# IntegratedSensor.net
KiCad netlist of a schematic drawn in EAGLE
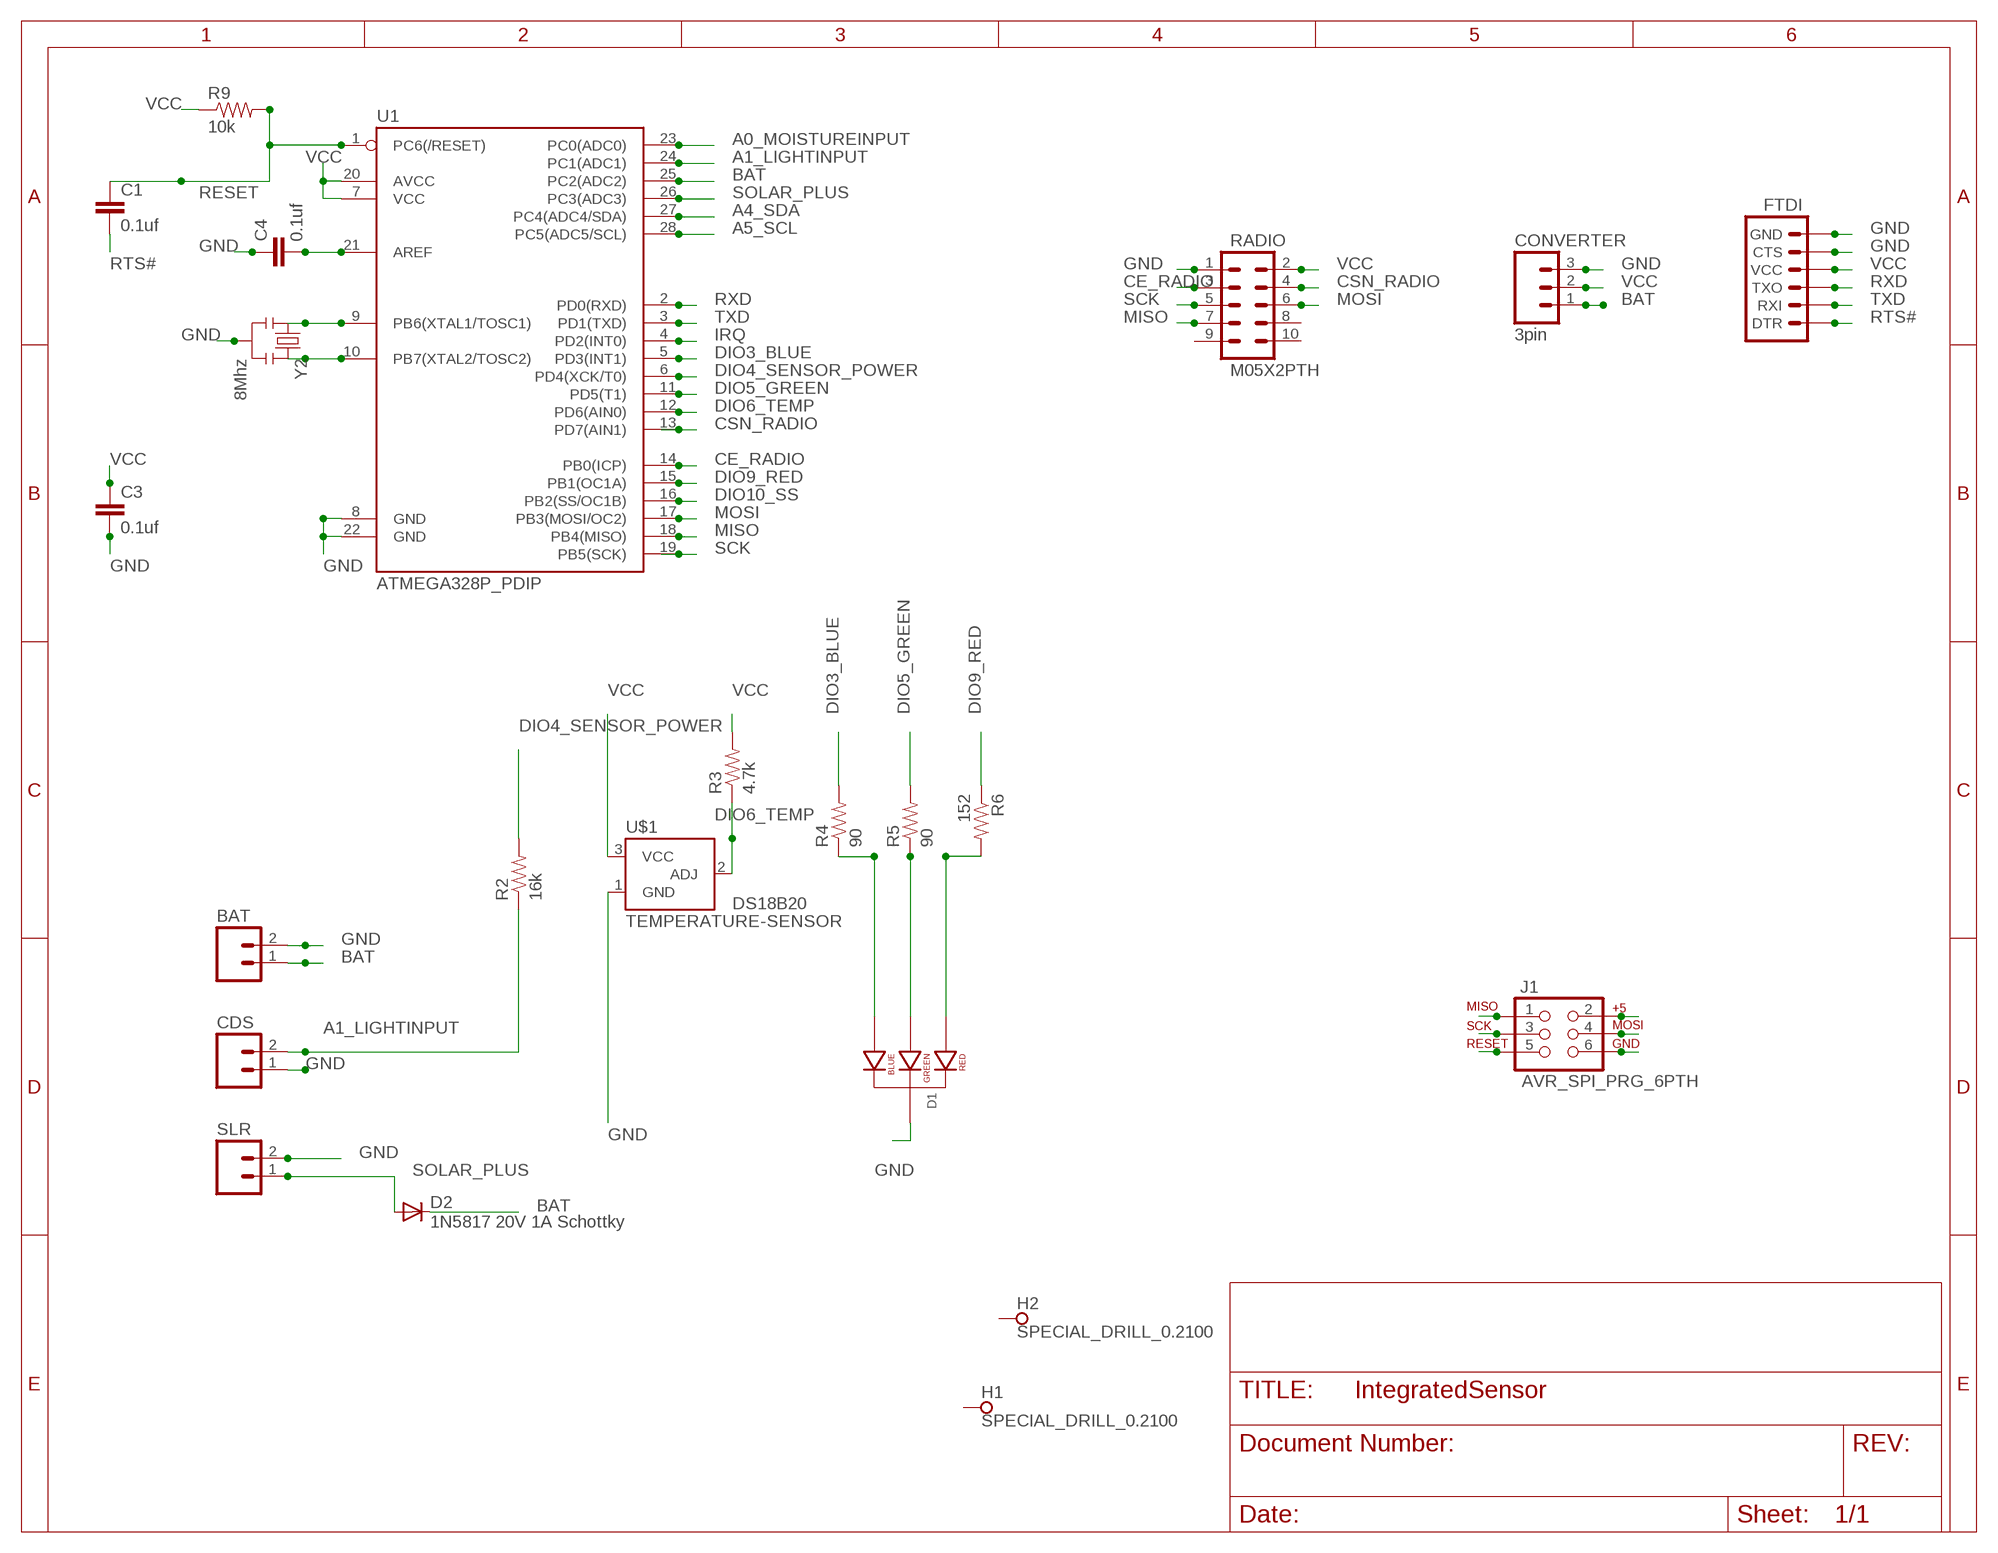
[diagram p0: schematic, sheet 1]

(export (version "E")
  (design (tool "Eeschema 10.0.6"))
  (components
    (comp (ref "BAT")
      (value "M02PTH")
      (footprint "eagle-import:1X02")
      (libsource (lib "eagle-import") (part "M02PTH"))
    )
    (comp (ref "C1")
      (value "0.1uf")
      (footprint "eagle-import:CAP-PTH-SMALL")
      (libsource (lib "eagle-import") (part "CAPPTH"))
    )
    (comp (ref "C3")
      (value "0.1uf")
      (footprint "eagle-import:CAP-PTH-SMALL")
      (libsource (lib "eagle-import") (part "CAPPTH"))
    )
    (comp (ref "C4")
      (value "0.1uf")
      (footprint "eagle-import:CAP-PTH-SMALL")
      (libsource (lib "eagle-import") (part "CAPPTH"))
    )
    (comp (ref "CDS")
      (value "M02PTH")
      (footprint "eagle-import:1X02")
      (libsource (lib "eagle-import") (part "M02PTH"))
    )
    (comp (ref "CONVERTER")
      (value "3pin")
      (footprint "eagle-import:1X03")
      (libsource (lib "eagle-import") (part "M03PTH"))
    )
    (comp (ref "D1")
      (value "LED-RGB-CC-THRUCLEAR")
      (footprint "eagle-import:LED-RGB-THRU")
      (libsource (lib "eagle-import") (part "LED-RGB-CC-THRUCLEAR"))
    )
    (comp (ref "D2")
      (value "1N5817 20V 1A Schottky")
      (footprint "eagle-import:DIODE-1N4001")
      (libsource (lib "eagle-import") (part "DIODEPTH"))
    )
    (comp (ref "FTDI")
      (value "ARDUINO_SERIAL_PROGRAMPTH")
      (footprint "eagle-import:1X06")
      (libsource (lib "eagle-import") (part "ARDUINO_SERIAL_PROGRAMPTH"))
    )
    (comp (ref "H1")
      (value "SPECIAL_DRILL_0.2100")
      (footprint "eagle-import:PAD_0.2100")
      (libsource (lib "eagle-import") (part "SPECIAL_DRILL_0.2100"))
    )
    (comp (ref "H2")
      (value "SPECIAL_DRILL_0.2100")
      (footprint "eagle-import:PAD_0.2100")
      (libsource (lib "eagle-import") (part "SPECIAL_DRILL_0.2100"))
    )
    (comp (ref "J1")
      (value "AVR_SPI_PRG_6PTH")
      (footprint "eagle-import:2X3")
      (libsource (lib "eagle-import") (part "AVR_SPI_PRG_6PTH"))
    )
    (comp (ref "R2")
      (value "16k")
      (footprint "eagle-import:1_6W-RES")
      (libsource (lib "eagle-import") (part "RESISTORPTH-1/6W"))
    )
    (comp (ref "R3")
      (value "4.7k")
      (footprint "eagle-import:1_6W-RES")
      (libsource (lib "eagle-import") (part "RESISTORPTH-1/6W"))
    )
    (comp (ref "R4")
      (value "90")
      (footprint "eagle-import:1_6W-RES")
      (libsource (lib "eagle-import") (part "RESISTORPTH-1/6W"))
    )
    (comp (ref "R5")
      (value "90")
      (footprint "eagle-import:1_6W-RES")
      (libsource (lib "eagle-import") (part "RESISTORPTH-1/6W"))
    )
    (comp (ref "R6")
      (value "152")
      (footprint "eagle-import:1_6W-RES")
      (libsource (lib "eagle-import") (part "RESISTORPTH-1/6W"))
    )
    (comp (ref "R9")
      (value "10k")
      (footprint "eagle-import:1_6W-RES")
      (libsource (lib "eagle-import") (part "RESISTORPTH-1/6W"))
    )
    (comp (ref "RADIO")
      (value "M05X2PTH")
      (footprint "eagle-import:AVR_ICSP")
      (libsource (lib "eagle-import") (part "M05X2PTH"))
    )
    (comp (ref "SLR")
      (value "M02PTH")
      (footprint "eagle-import:1X02")
      (libsource (lib "eagle-import") (part "M02PTH"))
    )
    (comp (ref "U$1")
      (value "TEMPERATURE-SENSOR")
      (footprint "eagle-import:TO-92")
      (fields (field (name "PARTNAME") "DS18B20"))
      (libsource (lib "eagle-import") (part "TEMPERATURE-SENSOR"))
    )
    (comp (ref "U1")
      (value "ATMEGA328P_PDIP")
      (footprint "eagle-import:DIL28-3")
      (libsource (lib "eagle-import") (part "ATMEGA328P_PDIP"))
    )
    (comp (ref "Y2")
      (value "8Mhz")
      (footprint "eagle-import:RESONATOR-PTH")
      (libsource (lib "eagle-import") (part "RESONATORPTH"))
    )
  )
  (nets
    (net (code "1") (name "/A0_MOISTUREINPUT") (class "Default")
      (node (ref "U1") (pin "23") (pinfunction "PC0(ADC0)_23") (pintype "bidirectional"))
    )
    (net (code "2") (name "/A1_LIGHTINPUT") (class "Default")
      (node (ref "CDS") (pin "2") (pinfunction "2_2") (pintype "passive"))
      (node (ref "R2") (pin "1") (pinfunction "1_1") (pintype "passive"))
      (node (ref "U1") (pin "24") (pinfunction "PC1(ADC1)_24") (pintype "bidirectional"))
    )
    (net (code "3") (name "/A4_SDA") (class "Default")
      (node (ref "U1") (pin "27") (pinfunction "PC4(ADC4/SDA)_27") (pintype "bidirectional"))
    )
    (net (code "4") (name "/A5_SCL") (class "Default")
      (node (ref "U1") (pin "28") (pinfunction "PC5(ADC5/SCL)_28") (pintype "bidirectional"))
    )
    (net (code "5") (name "/BAT") (class "Default")
      (node (ref "BAT") (pin "1") (pinfunction "1_1") (pintype "passive"))
      (node (ref "CONVERTER") (pin "1") (pinfunction "1_1") (pintype "passive"))
      (node (ref "D2") (pin "C") (pinfunction "C_C") (pintype "passive"))
      (node (ref "U1") (pin "25") (pinfunction "PC2(ADC2)_25") (pintype "bidirectional"))
    )
    (net (code "6") (name "/CE_RADIO") (class "Default")
      (node (ref "RADIO") (pin "3") (pinfunction "3_3") (pintype "passive"))
      (node (ref "U1") (pin "14") (pinfunction "PB0(ICP)_14") (pintype "bidirectional"))
    )
    (net (code "7") (name "/CSN_RADIO") (class "Default")
      (node (ref "RADIO") (pin "4") (pinfunction "4_4") (pintype "passive"))
      (node (ref "U1") (pin "13") (pinfunction "PD7(AIN1)_13") (pintype "bidirectional"))
    )
    (net (code "8") (name "/DIO3_BLUE") (class "Default")
      (node (ref "R4") (pin "2") (pinfunction "2_2") (pintype "passive"))
      (node (ref "U1") (pin "5") (pinfunction "PD3(INT1)_5") (pintype "bidirectional"))
    )
    (net (code "9") (name "/DIO4_SENSOR_POWER") (class "Default")
      (node (ref "R2") (pin "2") (pinfunction "2_2") (pintype "passive"))
      (node (ref "U1") (pin "6") (pinfunction "PD4(XCK/T0)_6") (pintype "bidirectional"))
    )
    (net (code "10") (name "/DIO5_GREEN") (class "Default")
      (node (ref "R5") (pin "2") (pinfunction "2_2") (pintype "passive"))
      (node (ref "U1") (pin "11") (pinfunction "PD5(T1)_11") (pintype "bidirectional"))
    )
    (net (code "11") (name "/DIO6_TEMP") (class "Default")
      (node (ref "R3") (pin "1") (pinfunction "1_1") (pintype "passive"))
      (node (ref "U$1") (pin "2") (pinfunction "ADJ_2") (pintype "bidirectional"))
      (node (ref "U1") (pin "12") (pinfunction "PD6(AIN0)_12") (pintype "bidirectional"))
    )
    (net (code "12") (name "/DIO9_RED") (class "Default")
      (node (ref "R6") (pin "1") (pinfunction "1_1") (pintype "passive"))
      (node (ref "U1") (pin "15") (pinfunction "PB1(OC1A)_15") (pintype "bidirectional"))
    )
    (net (code "13") (name "/DIO10_SS") (class "Default")
      (node (ref "U1") (pin "16") (pinfunction "PB2(SS/OC1B)_16") (pintype "bidirectional"))
    )
    (net (code "14") (name "/GND") (class "Default")
      (node (ref "BAT") (pin "2") (pinfunction "2_2") (pintype "passive"))
      (node (ref "C3") (pin "2") (pinfunction "2_2") (pintype "passive"))
      (node (ref "C4") (pin "1") (pinfunction "1_1") (pintype "passive"))
      (node (ref "CDS") (pin "1") (pinfunction "1_1") (pintype "passive"))
      (node (ref "CONVERTER") (pin "3") (pinfunction "3_3") (pintype "passive"))
      (node (ref "D1") (pin "2") (pinfunction "CATHODE_2") (pintype "bidirectional"))
      (node (ref "FTDI") (pin "5") (pinfunction "CTS_5") (pintype "passive"))
      (node (ref "FTDI") (pin "6") (pinfunction "GND_6") (pintype "passive"))
      (node (ref "J1") (pin "6") (pinfunction "6_6") (pintype "passive"))
      (node (ref "RADIO") (pin "1") (pinfunction "1_1") (pintype "passive"))
      (node (ref "SLR") (pin "2") (pinfunction "2_2") (pintype "passive"))
      (node (ref "U$1") (pin "1") (pinfunction "GND_1") (pintype "bidirectional"))
      (node (ref "U1") (pin "22") (pinfunction "GND_22") (pintype "bidirectional"))
      (node (ref "U1") (pin "8") (pinfunction "GND_8") (pintype "bidirectional"))
      (node (ref "Y2") (pin "2") (pinfunction "2_2") (pintype "passive"))
    )
    (net (code "15") (name "/IRQ") (class "Default")
      (node (ref "U1") (pin "4") (pinfunction "PD2(INT0)_4") (pintype "bidirectional"))
    )
    (net (code "16") (name "/MISO") (class "Default")
      (node (ref "J1") (pin "1") (pinfunction "1_1") (pintype "passive"))
      (node (ref "RADIO") (pin "7") (pinfunction "7_7") (pintype "passive"))
      (node (ref "U1") (pin "18") (pinfunction "PB4(MISO)_18") (pintype "bidirectional"))
    )
    (net (code "17") (name "/MOSI") (class "Default")
      (node (ref "J1") (pin "4") (pinfunction "4_4") (pintype "passive"))
      (node (ref "RADIO") (pin "6") (pinfunction "6_6") (pintype "passive"))
      (node (ref "U1") (pin "17") (pinfunction "PB3(MOSI/OC2)_17") (pintype "bidirectional"))
    )
    (net (code "18") (name "/RESET") (class "Default")
      (node (ref "C1") (pin "1") (pinfunction "1_1") (pintype "passive"))
      (node (ref "J1") (pin "5") (pinfunction "5_5") (pintype "passive"))
      (node (ref "R9") (pin "2") (pinfunction "2_2") (pintype "passive"))
      (node (ref "U1") (pin "1") (pinfunction "PC6(/RESET)_1") (pintype "bidirectional"))
    )
    (net (code "19") (name "/RTS#") (class "Default")
      (node (ref "C1") (pin "2") (pinfunction "2_2") (pintype "passive"))
      (node (ref "FTDI") (pin "1") (pinfunction "DTR_1") (pintype "passive"))
    )
    (net (code "20") (name "/RXD") (class "Default")
      (node (ref "FTDI") (pin "3") (pinfunction "TXO_3") (pintype "passive"))
      (node (ref "U1") (pin "2") (pinfunction "PD0(RXD)_2") (pintype "bidirectional"))
    )
    (net (code "21") (name "/SCK") (class "Default")
      (node (ref "J1") (pin "3") (pinfunction "3_3") (pintype "passive"))
      (node (ref "RADIO") (pin "5") (pinfunction "5_5") (pintype "passive"))
      (node (ref "U1") (pin "19") (pinfunction "PB5(SCK)_19") (pintype "bidirectional"))
    )
    (net (code "22") (name "/SOLAR_PLUS") (class "Default")
      (node (ref "D2") (pin "A") (pinfunction "A_A") (pintype "passive"))
      (node (ref "SLR") (pin "1") (pinfunction "1_1") (pintype "passive"))
      (node (ref "U1") (pin "26") (pinfunction "PC3(ADC3)_26") (pintype "bidirectional"))
    )
    (net (code "23") (name "/TXD") (class "Default")
      (node (ref "FTDI") (pin "2") (pinfunction "RXI_2") (pintype "passive"))
      (node (ref "U1") (pin "3") (pinfunction "PD1(TXD)_3") (pintype "bidirectional"))
    )
    (net (code "24") (name "/VCC") (class "Default")
      (node (ref "C3") (pin "1") (pinfunction "1_1") (pintype "passive"))
      (node (ref "CONVERTER") (pin "2") (pinfunction "2_2") (pintype "passive"))
      (node (ref "FTDI") (pin "4") (pinfunction "VCC_4") (pintype "passive"))
      (node (ref "J1") (pin "2") (pinfunction "2_2") (pintype "passive"))
      (node (ref "R3") (pin "2") (pinfunction "2_2") (pintype "passive"))
      (node (ref "R9") (pin "1") (pinfunction "1_1") (pintype "passive"))
      (node (ref "RADIO") (pin "2") (pinfunction "2_2") (pintype "passive"))
      (node (ref "U$1") (pin "3") (pinfunction "VCC_3") (pintype "bidirectional"))
      (node (ref "U1") (pin "20") (pinfunction "AVCC_20") (pintype "bidirectional"))
      (node (ref "U1") (pin "7") (pinfunction "VCC_7") (pintype "bidirectional"))
    )
    (net (code "25") (name "Net-(D1-BLUE_CATHODE)") (class "Default")
      (node (ref "D1") (pin "4") (pinfunction "BLUE_CATHODE_4") (pintype "bidirectional"))
      (node (ref "R4") (pin "1") (pinfunction "1_1") (pintype "passive"))
    )
    (net (code "26") (name "Net-(D1-GREEN_CATHODE)") (class "Default")
      (node (ref "D1") (pin "3") (pinfunction "GREEN_CATHODE_3") (pintype "bidirectional"))
      (node (ref "R5") (pin "1") (pinfunction "1_1") (pintype "passive"))
    )
    (net (code "27") (name "Net-(D1-RED_CATHODE)") (class "Default")
      (node (ref "D1") (pin "1") (pinfunction "RED_CATHODE_1") (pintype "bidirectional"))
      (node (ref "R6") (pin "2") (pinfunction "2_2") (pintype "passive"))
    )
    (net (code "28") (name "Net-(U1-AREF)") (class "Default")
      (node (ref "C4") (pin "2") (pinfunction "2_2") (pintype "passive"))
      (node (ref "U1") (pin "21") (pinfunction "AREF_21") (pintype "bidirectional"))
    )
    (net (code "29") (name "Net-(U1-PB6(XTAL1{slash}TOSC1))") (class "Default")
      (node (ref "U1") (pin "9") (pinfunction "PB6(XTAL1/TOSC1)_9") (pintype "bidirectional"))
      (node (ref "Y2") (pin "1") (pinfunction "1_1") (pintype "passive"))
    )
    (net (code "30") (name "Net-(U1-PB7(XTAL2{slash}TOSC2))") (class "Default")
      (node (ref "U1") (pin "10") (pinfunction "PB7(XTAL2/TOSC2)_10") (pintype "bidirectional"))
      (node (ref "Y2") (pin "3") (pinfunction "3_3") (pintype "passive"))
    )
    (net (code "31") (name "unconnected-(H1-Pad1)") (class "Default")
      (node (ref "H1") (pin "1") (pinfunction "1_1") (pintype "passive"))
    )
    (net (code "32") (name "unconnected-(H2-Pad1)") (class "Default")
      (node (ref "H2") (pin "1") (pinfunction "1_1") (pintype "passive"))
    )
    (net (code "33") (name "unconnected-(RADIO-Pad8)") (class "Default")
      (node (ref "RADIO") (pin "8") (pinfunction "8_8") (pintype "passive"))
    )
    (net (code "34") (name "unconnected-(RADIO-Pad9)") (class "Default")
      (node (ref "RADIO") (pin "9") (pinfunction "9_9") (pintype "passive"))
    )
    (net (code "35") (name "unconnected-(RADIO-Pad10)") (class "Default")
      (node (ref "RADIO") (pin "10") (pinfunction "10_10") (pintype "passive"))
    )
  )
)
